# motion-sensor.net
KiCad netlist of a schematic drawn in EAGLE
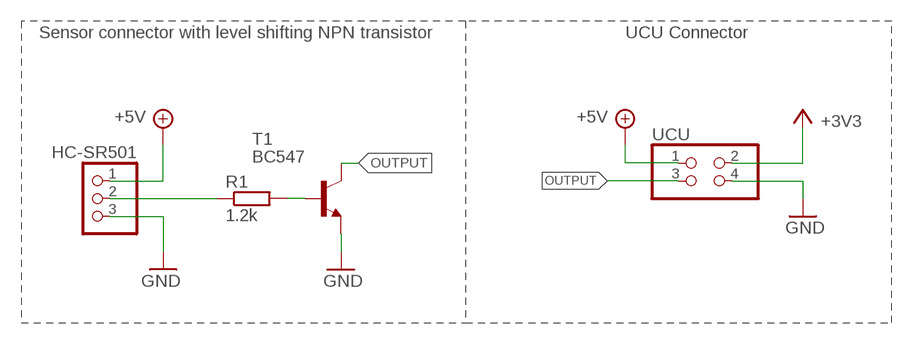
[diagram p0: schematic, sheet 1]

(export (version "E")
  (design (tool "Eeschema 10.0.6"))
  (components
    (comp (ref "HC-SR501")
      (value "PINHD-1X3")
      (footprint "eagle-import:1X03")
      (libsource (lib "eagle-import") (part "PINHD-1X3"))
    )
    (comp (ref "R1")
      (value "1.2k")
      (footprint "eagle-import:0204_7")
      (libsource (lib "eagle-import") (part "R-EU_0204/7"))
    )
    (comp (ref "T1")
      (value "BC547")
      (footprint "eagle-import:TO92")
      (libsource (lib "eagle-import") (part "BC547"))
    )
    (comp (ref "UCU")
      (value "PINHD-2X2")
      (footprint "eagle-import:2X02")
      (libsource (lib "eagle-import") (part "PINHD-2X2"))
    )
  )
  (nets
    (net (code "1") (name "+3V3") (class "Default")
      (node (ref "UCU") (pin "2") (pinfunction "2_2") (pintype "passive"))
    )
    (net (code "2") (name "+5V") (class "Default")
      (node (ref "HC-SR501") (pin "1") (pinfunction "1_1") (pintype "passive"))
      (node (ref "UCU") (pin "1") (pinfunction "1_1") (pintype "passive"))
    )
    (net (code "3") (name "GND") (class "Default")
      (node (ref "HC-SR501") (pin "3") (pinfunction "3_3") (pintype "passive"))
      (node (ref "T1") (pin "1") (pinfunction "E_1") (pintype "passive"))
      (node (ref "UCU") (pin "4") (pinfunction "4_4") (pintype "passive"))
    )
    (net (code "4") (name "Net-(HC-SR501-Pad2)") (class "Default")
      (node (ref "HC-SR501") (pin "2") (pinfunction "2_2") (pintype "passive"))
      (node (ref "R1") (pin "1") (pinfunction "1_1") (pintype "passive"))
    )
    (net (code "5") (name "Net-(T1-B)") (class "Default")
      (node (ref "R1") (pin "2") (pinfunction "2_2") (pintype "passive"))
      (node (ref "T1") (pin "2") (pinfunction "B_2") (pintype "passive"))
    )
    (net (code "6") (name "OUTPUT") (class "Default")
      (node (ref "T1") (pin "3") (pinfunction "C_3") (pintype "passive"))
      (node (ref "UCU") (pin "3") (pinfunction "3_3") (pintype "passive"))
    )
  )
)
